# RS485.net
KiCad netlist of a schematic drawn in Altium Designer
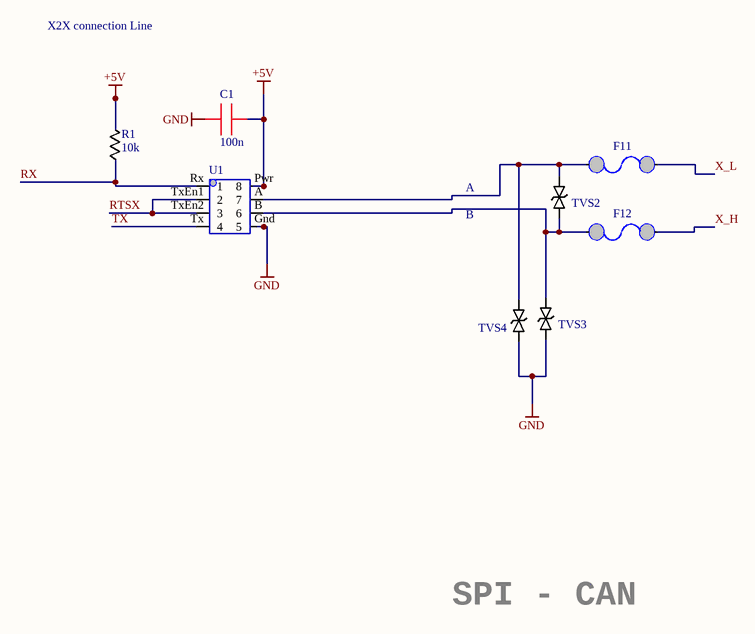
[diagram p0: RS485.SchDoc]

(export (version "E")
  (design (tool "Eeschema 10.0.6"))
  (components
    (comp (ref "C1")
      (value "100n")
      (footprint "0603_Cap")
      (fields (field (name "PART NUMBER") "CC0603ZRY5V9BB104"))
      (libsource (lib "kontr") (part "Capasitor 0805"))
    )
    (comp (ref "F11")
      (value "~")
      (footprint "1210_MF")
      (fields (field (name "PART NUMBER") "MF-USMF005-2"))
      (libsource (lib "kontr") (part "Fuse PTS"))
    )
    (comp (ref "F12")
      (value "~")
      (footprint "1210_MF")
      (fields (field (name "PART NUMBER") "MF-USMF005-2"))
      (libsource (lib "kontr") (part "Fuse PTS"))
    )
    (comp (ref "R1")
      (value "10k")
      (footprint "0603_Res")
      (fields (field (name "PART NUMBER") "RT0603FRE0710KL"))
      (libsource (lib "kontr") (part "Resistor 0805"))
    )
    (comp (ref "TVS2")
      (value "~")
      (footprint "DO-214AC")
      (fields (field (name "PART NUMBER") "SMAJ5.0CA"))
      (libsource (lib "kontr") (part "SMAJ5.0CA"))
    )
    (comp (ref "TVS3")
      (value "~")
      (footprint "DO-214AC")
      (fields (field (name "PART NUMBER") "SMAJ5.0CA"))
      (libsource (lib "kontr") (part "SMAJ5.0CA"))
    )
    (comp (ref "TVS4")
      (value "~")
      (footprint "DO-214AC")
      (fields (field (name "PART NUMBER") "SMAJ5.0CA"))
      (libsource (lib "kontr") (part "SMAJ5.0CA"))
    )
    (comp (ref "U1")
      (value "~")
      (footprint "EIA485")
      (fields (field (name "PART NUMBER") "SN65HVD3082EDR"))
      (libsource (lib "Schlib1") (part "MAX485"))
    )
  )
  (nets
    (net (code "1") (name "+5V") (class "Default")
      (node (ref "C1") (pin "2") (pinfunction "2_2") (pintype "passive"))
      (node (ref "R1") (pin "2") (pintype "passive"))
      (node (ref "U1") (pin "Pwr") (pinfunction "8_Pwr") (pintype "passive"))
    )
    (net (code "2") (name "/RTSX") (class "Default")
      (node (ref "U1") (pin "TxEn1") (pinfunction "2_TxEn1") (pintype "passive"))
      (node (ref "U1") (pin "TxEn2") (pinfunction "3_TxEn2") (pintype "passive"))
    )
    (net (code "3") (name "/RX") (class "Default")
      (node (ref "R1") (pin "1") (pintype "passive"))
      (node (ref "U1") (pin "Rx") (pinfunction "1_Rx") (pintype "passive"))
    )
    (net (code "4") (name "/TX") (class "Default")
      (node (ref "U1") (pin "Tx") (pinfunction "4_Tx") (pintype "passive"))
    )
    (net (code "5") (name "/X_H") (class "Default")
      (node (ref "F12") (pin "1") (pinfunction "1_1") (pintype "passive"))
    )
    (net (code "6") (name "/X_L") (class "Default")
      (node (ref "F11") (pin "1") (pinfunction "1_1") (pintype "passive"))
    )
    (net (code "7") (name "GND") (class "Default")
      (node (ref "C1") (pin "1") (pinfunction "1_1") (pintype "passive"))
      (node (ref "TVS3") (pin "1") (pinfunction "1_1") (pintype "passive"))
      (node (ref "TVS4") (pin "1") (pinfunction "1_1") (pintype "passive"))
      (node (ref "U1") (pin "Gnd") (pinfunction "5_Gnd") (pintype "passive"))
    )
    (net (code "8") (name "Net-(U1-6)") (class "Default")
      (node (ref "F12") (pin "2") (pinfunction "2_2") (pintype "passive"))
      (node (ref "TVS2") (pin "1") (pinfunction "1_1") (pintype "passive"))
      (node (ref "TVS3") (pin "2") (pinfunction "2_2") (pintype "passive"))
      (node (ref "U1") (pin "B") (pinfunction "6_B") (pintype "passive"))
    )
    (net (code "9") (name "Net-(U1-7)") (class "Default")
      (node (ref "F11") (pin "2") (pinfunction "2_2") (pintype "passive"))
      (node (ref "TVS2") (pin "2") (pinfunction "2_2") (pintype "passive"))
      (node (ref "TVS4") (pin "2") (pinfunction "2_2") (pintype "passive"))
      (node (ref "U1") (pin "A") (pinfunction "7_A") (pintype "passive"))
    )
  )
)
